# CH340G_PTT.net
KiCad netlist of a schematic drawn in Altium Designer
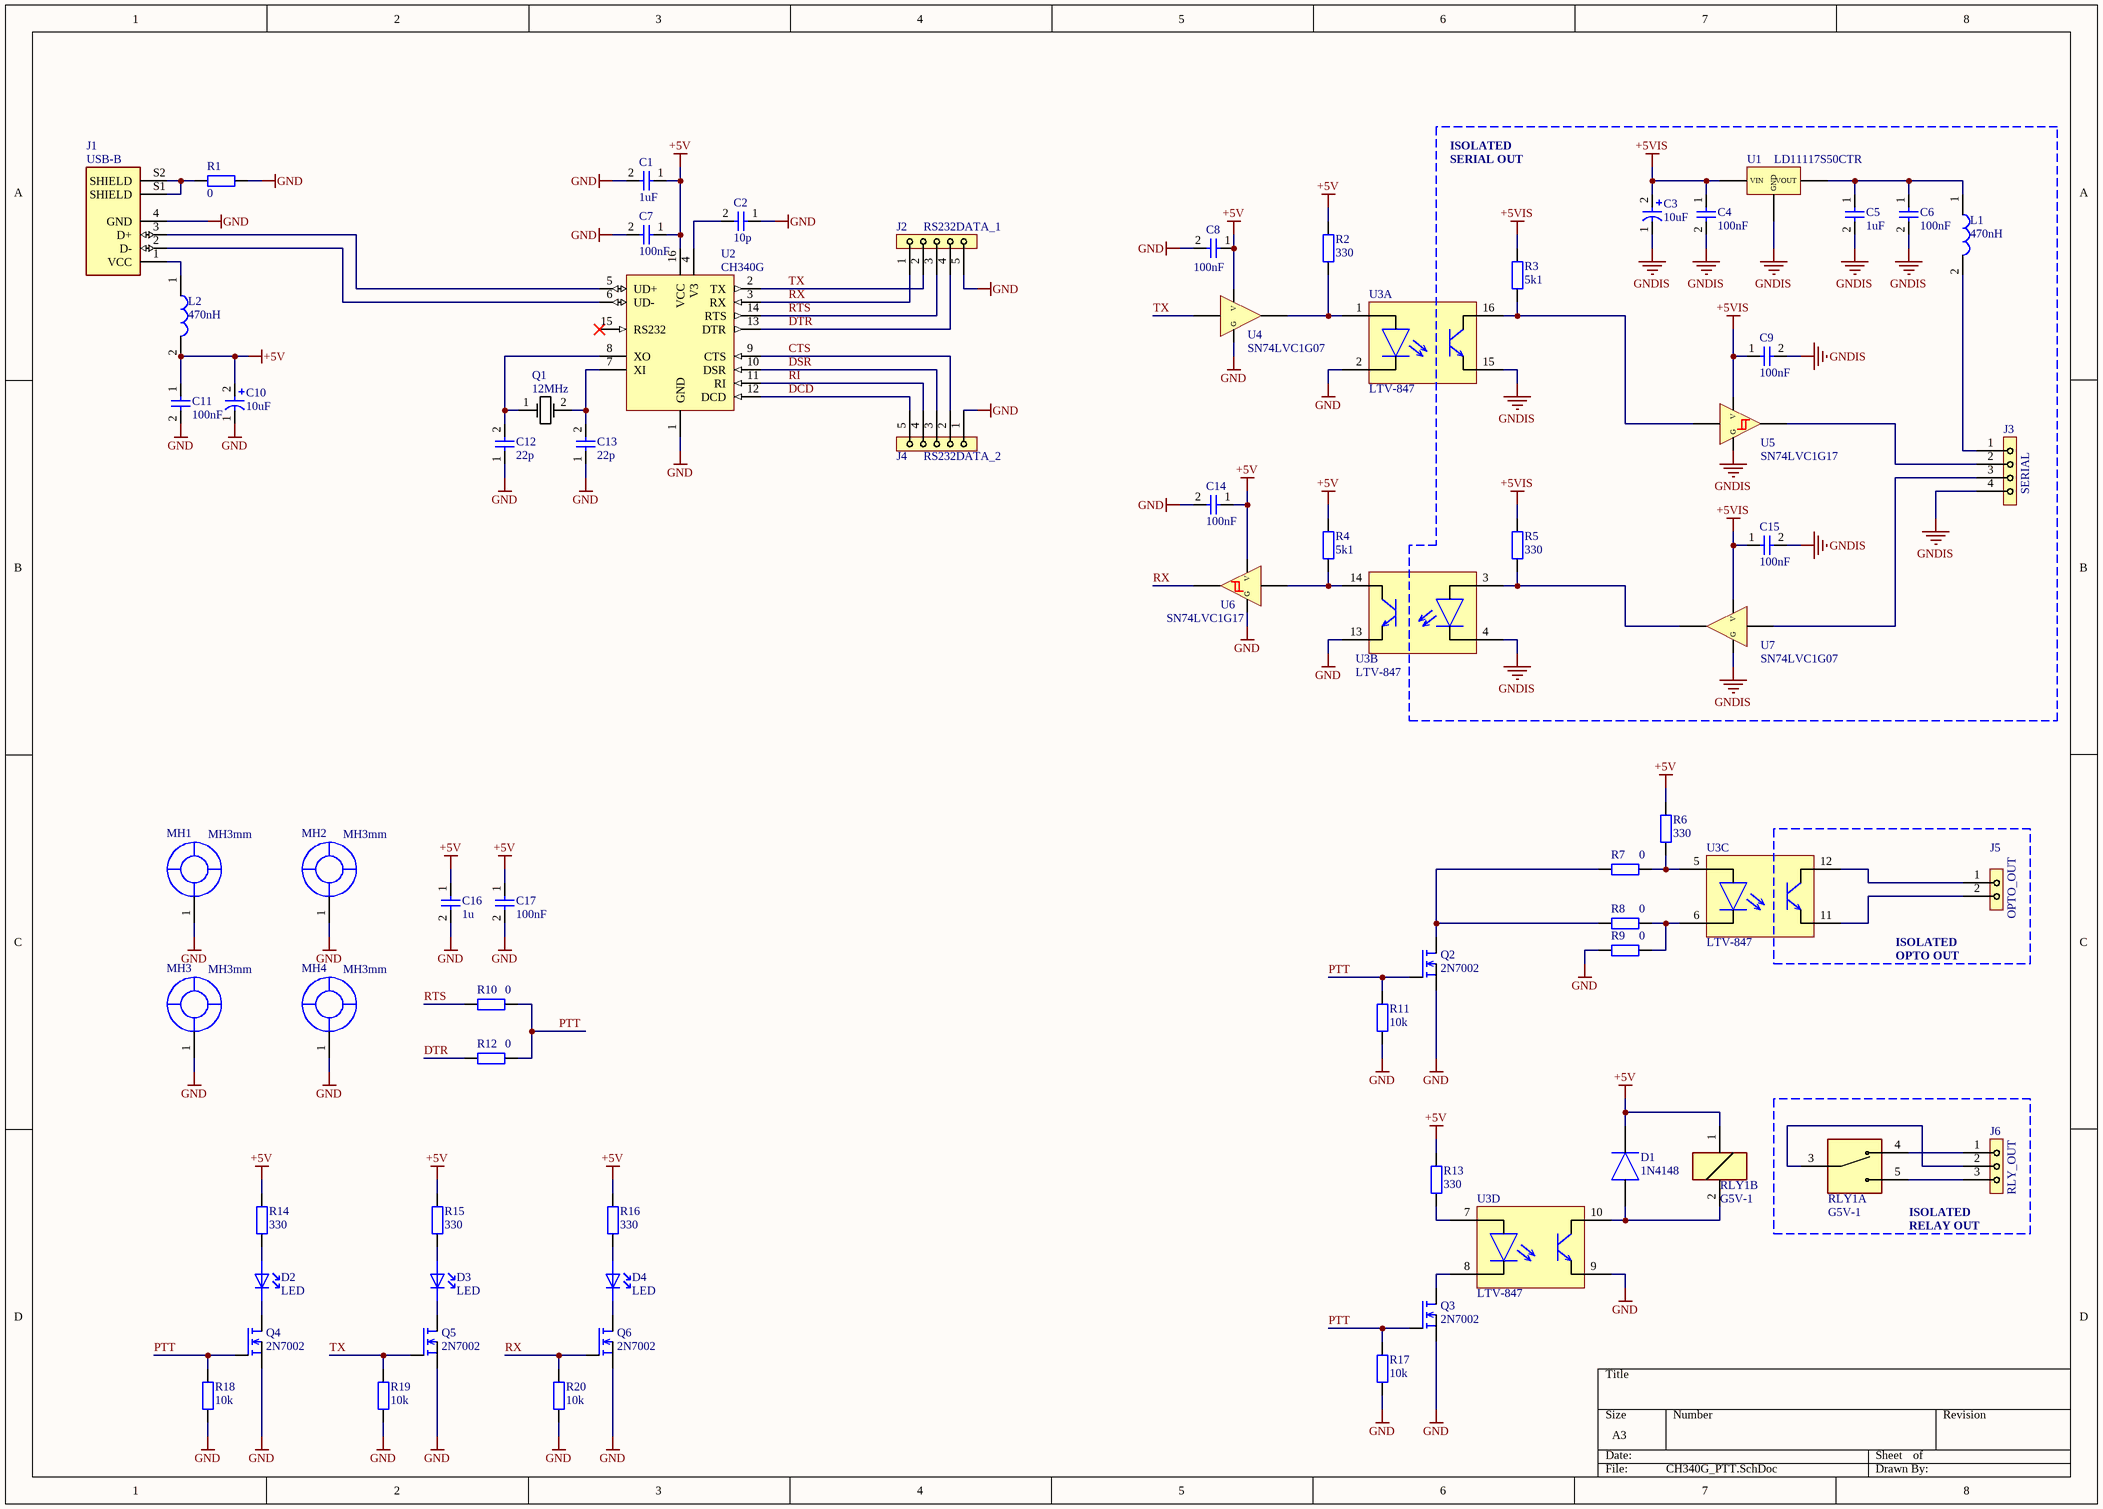
[diagram p0: CH340G_PTT.SchDoc]

(export (version "E")
  (design (tool "Eeschema 10.0.6"))
  (components
    (comp (ref "C1")
      (value "1uF")
      (footprint "FP-1206-L_3_2_0_2-W_1_6_0-IPC_B")
      (libsource (lib "COMM_SHIELD_STUFF") (part "cap_unpol"))
    )
    (comp (ref "C2")
      (value "10p")
      (footprint "FP-1206-L_3_2_0_2-W_1_6_0-IPC_B")
      (libsource (lib "COMM_SHIELD_STUFF") (part "cap_unpol"))
    )
    (comp (ref "C3")
      (value "10uF")
      (footprint "CAP_SMD_6.3x7.7mm")
      (libsource (lib "COMM_SHIELD_STUFF") (part "cap_pol"))
    )
    (comp (ref "C4")
      (value "100nF")
      (footprint "FP-1206-L_3_2_0_2-W_1_6_0-IPC_B")
      (libsource (lib "COMM_SHIELD_STUFF") (part "cap_unpol"))
    )
    (comp (ref "C5")
      (value "1uF")
      (footprint "FP-1206-L_3_2_0_2-W_1_6_0-IPC_B")
      (libsource (lib "COMM_SHIELD_STUFF") (part "cap_unpol"))
    )
    (comp (ref "C6")
      (value "100nF")
      (footprint "FP-1206-L_3_2_0_2-W_1_6_0-IPC_B")
      (libsource (lib "COMM_SHIELD_STUFF") (part "cap_unpol"))
    )
    (comp (ref "C7")
      (value "100nF")
      (footprint "FP-1206-L_3_2_0_2-W_1_6_0-IPC_B")
      (libsource (lib "COMM_SHIELD_STUFF") (part "cap_unpol"))
    )
    (comp (ref "C8")
      (value "100nF")
      (footprint "FP-1206-L_3_2_0_2-W_1_6_0-IPC_B")
      (libsource (lib "COMM_SHIELD_STUFF") (part "cap_unpol"))
    )
    (comp (ref "C9")
      (value "100nF")
      (footprint "FP-1206-L_3_2_0_2-W_1_6_0-IPC_B")
      (libsource (lib "COMM_SHIELD_STUFF") (part "cap_unpol"))
    )
    (comp (ref "C10")
      (value "10uF")
      (footprint "CAP_SMD_6.3x7.7mm")
      (libsource (lib "COMM_SHIELD_STUFF") (part "cap_pol"))
    )
    (comp (ref "C11")
      (value "100nF")
      (footprint "FP-1206-L_3_2_0_2-W_1_6_0-IPC_B")
      (libsource (lib "COMM_SHIELD_STUFF") (part "cap_unpol"))
    )
    (comp (ref "C12")
      (value "22p")
      (footprint "FP-1206-L_3_2_0_2-W_1_6_0-IPC_B")
      (libsource (lib "COMM_SHIELD_STUFF") (part "cap_unpol"))
    )
    (comp (ref "C13")
      (value "22p")
      (footprint "FP-1206-L_3_2_0_2-W_1_6_0-IPC_B")
      (libsource (lib "COMM_SHIELD_STUFF") (part "cap_unpol"))
    )
    (comp (ref "C14")
      (value "100nF")
      (footprint "FP-1206-L_3_2_0_2-W_1_6_0-IPC_B")
      (libsource (lib "COMM_SHIELD_STUFF") (part "cap_unpol"))
    )
    (comp (ref "C15")
      (value "100nF")
      (footprint "FP-1206-L_3_2_0_2-W_1_6_0-IPC_B")
      (libsource (lib "COMM_SHIELD_STUFF") (part "cap_unpol"))
    )
    (comp (ref "C16")
      (value "1u")
      (footprint "FP-1206-L_3_2_0_2-W_1_6_0-IPC_B")
      (libsource (lib "COMM_SHIELD_STUFF") (part "cap_unpol"))
    )
    (comp (ref "C17")
      (value "100nF")
      (footprint "FP-1206-L_3_2_0_2-W_1_6_0-IPC_B")
      (libsource (lib "COMM_SHIELD_STUFF") (part "cap_unpol"))
    )
    (comp (ref "D1")
      (value "1N4148")
      (footprint "SOD80C")
      (libsource (lib "COMM_SHIELD_STUFF") (part "1N4148"))
    )
    (comp (ref "D2")
      (value "LED")
      (footprint "LED_3mm")
      (libsource (lib "COMM_SHIELD_STUFF") (part "LED_3mm"))
    )
    (comp (ref "D3")
      (value "LED")
      (footprint "LED_3mm")
      (libsource (lib "COMM_SHIELD_STUFF") (part "LED_3mm"))
    )
    (comp (ref "D4")
      (value "LED")
      (footprint "LED_3mm")
      (libsource (lib "COMM_SHIELD_STUFF") (part "LED_3mm"))
    )
    (comp (ref "J1")
      (value "USB-B")
      (footprint "USB-B")
      (libsource (lib "COMM_SHIELD_STUFF") (part "USB-B-THT"))
    )
    (comp (ref "J2")
      (value "RS232DATA_1")
      (footprint "PIN_HEADER_1L_5P")
      (libsource (lib "COMM_SHIELD_STUFF") (part "PIN_HEADER_1L_5P"))
    )
    (comp (ref "J3")
      (value "SERIAL")
      (footprint "PIN_HEADER_1L_4P")
      (libsource (lib "COMM_SHIELD_STUFF") (part "PIN_HEADER_1L_4P"))
    )
    (comp (ref "J4")
      (value "RS232DATA_2")
      (footprint "PIN_HEADER_1L_5P")
      (libsource (lib "") (part "PIN_HEADER_1L_5P_1"))
    )
    (comp (ref "J5")
      (value "OPTO_OUT")
      (footprint "PIN_HEADER_1L_2P")
      (libsource (lib "COMM_SHIELD_STUFF") (part "PIN_HEADER_1L_2P"))
    )
    (comp (ref "J6")
      (value "RLY_OUT")
      (footprint "PIN_HEADER_1L_3P")
      (libsource (lib "COMM_SHIELD_STUFF") (part "PIN_HEADER_1L_3P"))
    )
    (comp (ref "L1")
      (value "470nH")
      (footprint "INDC2012X105N")
      (libsource (lib "COMM_SHIELD_STUFF") (part "Inductance"))
    )
    (comp (ref "L2")
      (value "470nH")
      (footprint "INDC2012X105N")
      (libsource (lib "COMM_SHIELD_STUFF") (part "Inductance"))
    )
    (comp (ref "MH1")
      (value "MH3mm")
      (footprint "MOUNTING_HOLE_GROUNDED")
      (description "3.5mm grounded mounting hole")
      (libsource (lib "COMM_SHIELD_STUFF") (part "MOUNTING_HOLE_3.5mm_1"))
    )
    (comp (ref "MH2")
      (value "MH3mm")
      (footprint "MOUNTING_HOLE_GROUNDED")
      (description "3.5mm grounded mounting hole")
      (libsource (lib "COMM_SHIELD_STUFF") (part "MOUNTING_HOLE_3.5mm_1"))
    )
    (comp (ref "MH3")
      (value "MH3mm")
      (footprint "MOUNTING_HOLE_GROUNDED")
      (description "3.5mm grounded mounting hole")
      (libsource (lib "COMM_SHIELD_STUFF") (part "MOUNTING_HOLE_3.5mm_1"))
    )
    (comp (ref "MH4")
      (value "MH3mm")
      (footprint "MOUNTING_HOLE_GROUNDED")
      (description "3.5mm grounded mounting hole")
      (libsource (lib "COMM_SHIELD_STUFF") (part "MOUNTING_HOLE_3.5mm_1"))
    )
    (comp (ref "Q1")
      (value "12MHz")
      (footprint "XTAL_SMD")
      (libsource (lib "COMM_SHIELD_STUFF") (part "Quartz Crystal"))
    )
    (comp (ref "Q2")
      (value "2N7002")
      (footprint "SOT23")
      (libsource (lib "COMM_SHIELD_STUFF") (part "BSS123"))
    )
    (comp (ref "Q3")
      (value "2N7002")
      (footprint "SOT23")
      (libsource (lib "COMM_SHIELD_STUFF") (part "BSS123"))
    )
    (comp (ref "Q4")
      (value "2N7002")
      (footprint "SOT23")
      (libsource (lib "COMM_SHIELD_STUFF") (part "BSS123"))
    )
    (comp (ref "Q5")
      (value "2N7002")
      (footprint "SOT23")
      (libsource (lib "COMM_SHIELD_STUFF") (part "BSS123"))
    )
    (comp (ref "Q6")
      (value "2N7002")
      (footprint "SOT23")
      (libsource (lib "COMM_SHIELD_STUFF") (part "BSS123"))
    )
    (comp (ref "R1")
      (value "0")
      (footprint "FP-CRCW1206-e3-IPC_B")
      (description "EU symbol")
      (fields (field (name "RESISTANCE") "0"))
      (libsource (lib "COMM_SHIELD_STUFF") (part "Resistor"))
    )
    (comp (ref "R2")
      (value "Resistor")
      (footprint "FP-CRCW1206-e3-IPC_B")
      (description "EU symbol")
      (fields (field (name "RESISTANCE") "330"))
      (libsource (lib "COMM_SHIELD_STUFF") (part "Resistor"))
    )
    (comp (ref "R3")
      (value "Resistor")
      (footprint "FP-CRCW1206-e3-IPC_B")
      (description "EU symbol")
      (fields (field (name "RESISTANCE") "5k1"))
      (libsource (lib "COMM_SHIELD_STUFF") (part "Resistor"))
    )
    (comp (ref "R4")
      (value "Resistor")
      (footprint "FP-CRCW1206-e3-IPC_B")
      (description "EU symbol")
      (fields (field (name "RESISTANCE") "5k1"))
      (libsource (lib "COMM_SHIELD_STUFF") (part "Resistor"))
    )
    (comp (ref "R5")
      (value "Resistor")
      (footprint "FP-CRCW1206-e3-IPC_B")
      (description "EU symbol")
      (fields (field (name "RESISTANCE") "330"))
      (libsource (lib "COMM_SHIELD_STUFF") (part "Resistor"))
    )
    (comp (ref "R6")
      (value "Resistor")
      (footprint "FP-CRCW1206-e3-IPC_B")
      (description "EU symbol")
      (fields (field (name "RESISTANCE") "330"))
      (libsource (lib "COMM_SHIELD_STUFF") (part "Resistor"))
    )
    (comp (ref "R7")
      (value "Resistor")
      (footprint "FP-CRCW1206-e3-IPC_B")
      (description "EU symbol")
      (fields (field (name "RESISTANCE") "0"))
      (libsource (lib "COMM_SHIELD_STUFF") (part "Resistor"))
    )
    (comp (ref "R8")
      (value "Resistor")
      (footprint "FP-CRCW1206-e3-IPC_B")
      (description "EU symbol")
      (fields (field (name "RESISTANCE") "0"))
      (libsource (lib "COMM_SHIELD_STUFF") (part "Resistor"))
    )
    (comp (ref "R9")
      (value "Resistor")
      (footprint "FP-CRCW1206-e3-IPC_B")
      (description "EU symbol")
      (fields (field (name "RESISTANCE") "0"))
      (libsource (lib "COMM_SHIELD_STUFF") (part "Resistor"))
    )
    (comp (ref "R10")
      (value "Resistor")
      (footprint "FP-CRCW1206-e3-IPC_B")
      (description "EU symbol")
      (fields (field (name "RESISTANCE") "0"))
      (libsource (lib "COMM_SHIELD_STUFF") (part "Resistor"))
    )
    (comp (ref "R11")
      (value "Resistor")
      (footprint "FP-CRCW1206-e3-IPC_B")
      (description "EU symbol")
      (fields (field (name "RESISTANCE") "10k"))
      (libsource (lib "COMM_SHIELD_STUFF") (part "Resistor"))
    )
    (comp (ref "R12")
      (value "Resistor")
      (footprint "FP-CRCW1206-e3-IPC_B")
      (description "EU symbol")
      (fields (field (name "RESISTANCE") "0"))
      (libsource (lib "COMM_SHIELD_STUFF") (part "Resistor"))
    )
    (comp (ref "R13")
      (value "Resistor")
      (footprint "FP-CRCW1206-e3-IPC_B")
      (description "EU symbol")
      (fields (field (name "RESISTANCE") "330"))
      (libsource (lib "COMM_SHIELD_STUFF") (part "Resistor"))
    )
    (comp (ref "R14")
      (value "Resistor")
      (footprint "FP-CRCW1206-e3-IPC_B")
      (description "EU symbol")
      (fields (field (name "RESISTANCE") "330"))
      (libsource (lib "COMM_SHIELD_STUFF") (part "Resistor"))
    )
    (comp (ref "R15")
      (value "Resistor")
      (footprint "FP-CRCW1206-e3-IPC_B")
      (description "EU symbol")
      (fields (field (name "RESISTANCE") "330"))
      (libsource (lib "COMM_SHIELD_STUFF") (part "Resistor"))
    )
    (comp (ref "R16")
      (value "Resistor")
      (footprint "FP-CRCW1206-e3-IPC_B")
      (description "EU symbol")
      (fields (field (name "RESISTANCE") "330"))
      (libsource (lib "COMM_SHIELD_STUFF") (part "Resistor"))
    )
    (comp (ref "R17")
      (value "Resistor")
      (footprint "FP-CRCW1206-e3-IPC_B")
      (description "EU symbol")
      (fields (field (name "RESISTANCE") "10k"))
      (libsource (lib "COMM_SHIELD_STUFF") (part "Resistor"))
    )
    (comp (ref "R18")
      (value "Resistor")
      (footprint "FP-CRCW1206-e3-IPC_B")
      (description "EU symbol")
      (fields (field (name "RESISTANCE") "10k"))
      (libsource (lib "COMM_SHIELD_STUFF") (part "Resistor"))
    )
    (comp (ref "R19")
      (value "Resistor")
      (footprint "FP-CRCW1206-e3-IPC_B")
      (description "EU symbol")
      (fields (field (name "RESISTANCE") "10k"))
      (libsource (lib "COMM_SHIELD_STUFF") (part "Resistor"))
    )
    (comp (ref "R20")
      (value "Resistor")
      (footprint "FP-CRCW1206-e3-IPC_B")
      (description "EU symbol")
      (fields (field (name "RESISTANCE") "10k"))
      (libsource (lib "COMM_SHIELD_STUFF") (part "Resistor"))
    )
    (comp (ref "RLY1")
      (value "G5V-1")
      (footprint "OMRON-G5V-1")
      (libsource (lib "COMM_SHIELD_STUFF") (part "RELAY_GENERIC_SPDT"))
    )
    (comp (ref "U1")
      (value "LD11117S50CTR")
      (footprint "SOT230P700X180-4N")
      (libsource (lib "COMM_SHIELD_STUFF") (part "LD11117S50CTR"))
    )
    (comp (ref "U2")
      (value "CH340G")
      (footprint "SOIC16")
      (libsource (lib "COMM_SHIELD_STUFF") (part "CH340G"))
    )
    (comp (ref "U3") (value "LTV-847") (footprint "DIP16") (libsource (lib "") (part "LTV-847_1")))
    (comp (ref "U4")
      (value "SN74LVC1G07")
      (footprint "SOT95P280X145-5N")
      (libsource (lib "COMM_SHIELD_STUFF") (part "SN74LVC1G07"))
    )
    (comp (ref "U5")
      (value "SN74LVC1G17")
      (footprint "SOT95P280X145-5N")
      (libsource (lib "COMM_SHIELD_STUFF") (part "SN74LVC1G17"))
    )
    (comp (ref "U6")
      (value "SN74LVC1G17")
      (footprint "SOT95P280X145-5N")
      (libsource (lib "COMM_SHIELD_STUFF") (part "SN74LVC1G17"))
    )
    (comp (ref "U7")
      (value "SN74LVC1G07")
      (footprint "SOT95P280X145-5N")
      (libsource (lib "COMM_SHIELD_STUFF") (part "SN74LVC1G07"))
    )
  )
  (nets
    (net (code "1") (name "+5V") (class "Default")
      (node (ref "C1") (pin "1") (pinfunction "1_1") (pintype "passive"))
      (node (ref "C10") (pin "2") (pinfunction "2_2") (pintype "passive"))
      (node (ref "C11") (pin "1") (pinfunction "1_1") (pintype "passive"))
      (node (ref "C14") (pin "1") (pinfunction "1_1") (pintype "passive"))
      (node (ref "C16") (pin "1") (pinfunction "1_1") (pintype "passive"))
      (node (ref "C17") (pin "1") (pinfunction "1_1") (pintype "passive"))
      (node (ref "C7") (pin "1") (pinfunction "1_1") (pintype "passive"))
      (node (ref "C8") (pin "1") (pinfunction "1_1") (pintype "passive"))
      (node (ref "D1") (pin "2") (pinfunction "K_2") (pintype "passive"))
      (node (ref "L2") (pin "2") (pinfunction "2_2") (pintype "passive"))
      (node (ref "R13") (pin "2") (pinfunction "2_2") (pintype "passive"))
      (node (ref "R14") (pin "2") (pinfunction "2_2") (pintype "passive"))
      (node (ref "R15") (pin "2") (pinfunction "2_2") (pintype "passive"))
      (node (ref "R16") (pin "2") (pinfunction "2_2") (pintype "passive"))
      (node (ref "R2") (pin "2") (pinfunction "2_2") (pintype "passive"))
      (node (ref "R4") (pin "2") (pinfunction "2_2") (pintype "passive"))
      (node (ref "R6") (pin "2") (pinfunction "2_2") (pintype "passive"))
      (node (ref "RLY1") (pin "1") (pinfunction "1_1") (pintype "passive"))
      (node (ref "U2") (pin "16") (pinfunction "VCC_16") (pintype "passive"))
      (node (ref "U4") (pin "5") (pinfunction "V_5") (pintype "passive"))
      (node (ref "U6") (pin "5") (pinfunction "V_5") (pintype "passive"))
    )
    (net (code "2") (name "+5VIS") (class "Default")
      (node (ref "C15") (pin "1") (pinfunction "1_1") (pintype "passive"))
      (node (ref "C3") (pin "2") (pinfunction "2_2") (pintype "passive"))
      (node (ref "C4") (pin "1") (pinfunction "1_1") (pintype "passive"))
      (node (ref "C9") (pin "1") (pinfunction "1_1") (pintype "passive"))
      (node (ref "R3") (pin "2") (pinfunction "2_2") (pintype "passive"))
      (node (ref "R5") (pin "1") (pinfunction "1_1") (pintype "passive"))
      (node (ref "U1") (pin "3") (pinfunction "VIN_3") (pintype "passive"))
      (node (ref "U5") (pin "5") (pinfunction "V_5") (pintype "passive"))
      (node (ref "U7") (pin "5") (pinfunction "V_5") (pintype "passive"))
    )
    (net (code "3") (name "/CTS") (class "Default")
      (node (ref "J4") (pin "2") (pinfunction "2_2") (pintype "passive"))
      (node (ref "U2") (pin "9") (pinfunction "CTS_9") (pintype "input"))
    )
    (net (code "4") (name "/DCD") (class "Default")
      (node (ref "J4") (pin "5") (pinfunction "5_5") (pintype "passive"))
      (node (ref "U2") (pin "12") (pinfunction "DCD_12") (pintype "input"))
    )
    (net (code "5") (name "/DSR") (class "Default")
      (node (ref "J4") (pin "3") (pinfunction "3_3") (pintype "passive"))
      (node (ref "U2") (pin "10") (pinfunction "DSR_10") (pintype "input"))
    )
    (net (code "6") (name "/DTR") (class "Default")
      (node (ref "J2") (pin "4") (pinfunction "4_4") (pintype "passive"))
      (node (ref "R12") (pin "1") (pinfunction "1_1") (pintype "passive"))
      (node (ref "U2") (pin "13") (pinfunction "DTR_13") (pintype "output"))
    )
    (net (code "7") (name "/PTT") (class "Default")
      (node (ref "Q2") (pin "1") (pinfunction "G_1") (pintype "passive"))
      (node (ref "Q3") (pin "1") (pinfunction "G_1") (pintype "passive"))
      (node (ref "Q4") (pin "1") (pinfunction "G_1") (pintype "passive"))
      (node (ref "R10") (pin "2") (pinfunction "2_2") (pintype "passive"))
      (node (ref "R11") (pin "2") (pinfunction "2_2") (pintype "passive"))
      (node (ref "R12") (pin "2") (pinfunction "2_2") (pintype "passive"))
      (node (ref "R17") (pin "2") (pinfunction "2_2") (pintype "passive"))
      (node (ref "R18") (pin "2") (pinfunction "2_2") (pintype "passive"))
    )
    (net (code "8") (name "/RI") (class "Default")
      (node (ref "J4") (pin "4") (pinfunction "4_4") (pintype "passive"))
      (node (ref "U2") (pin "11") (pinfunction "RI_11") (pintype "input"))
    )
    (net (code "9") (name "/RTS") (class "Default")
      (node (ref "J2") (pin "3") (pinfunction "3_3") (pintype "passive"))
      (node (ref "R10") (pin "1") (pinfunction "1_1") (pintype "passive"))
      (node (ref "U2") (pin "14") (pinfunction "RTS_14") (pintype "output"))
    )
    (net (code "10") (name "/RX") (class "Default")
      (node (ref "J2") (pin "1") (pinfunction "1_1") (pintype "passive"))
      (node (ref "Q6") (pin "1") (pinfunction "G_1") (pintype "passive"))
      (node (ref "R20") (pin "2") (pinfunction "2_2") (pintype "passive"))
      (node (ref "U2") (pin "3") (pinfunction "RX_3") (pintype "input"))
      (node (ref "U6") (pin "4") (pinfunction "Y_4") (pintype "passive"))
    )
    (net (code "11") (name "/TX") (class "Default")
      (node (ref "J2") (pin "2") (pinfunction "2_2") (pintype "passive"))
      (node (ref "Q5") (pin "1") (pinfunction "G_1") (pintype "passive"))
      (node (ref "R19") (pin "2") (pinfunction "2_2") (pintype "passive"))
      (node (ref "U2") (pin "2") (pinfunction "TX_2") (pintype "output"))
      (node (ref "U4") (pin "2") (pinfunction "A_2") (pintype "passive"))
    )
    (net (code "12") (name "GND") (class "Default")
      (node (ref "C1") (pin "2") (pinfunction "2_2") (pintype "passive"))
      (node (ref "C10") (pin "1") (pinfunction "1_1") (pintype "passive"))
      (node (ref "C11") (pin "2") (pinfunction "2_2") (pintype "passive"))
      (node (ref "C12") (pin "1") (pinfunction "1_1") (pintype "passive"))
      (node (ref "C13") (pin "1") (pinfunction "1_1") (pintype "passive"))
      (node (ref "C14") (pin "2") (pinfunction "2_2") (pintype "passive"))
      (node (ref "C16") (pin "2") (pinfunction "2_2") (pintype "passive"))
      (node (ref "C17") (pin "2") (pinfunction "2_2") (pintype "passive"))
      (node (ref "C2") (pin "1") (pinfunction "1_1") (pintype "passive"))
      (node (ref "C7") (pin "2") (pinfunction "2_2") (pintype "passive"))
      (node (ref "C8") (pin "2") (pinfunction "2_2") (pintype "passive"))
      (node (ref "J1") (pin "4") (pinfunction "GND_4") (pintype "power_in"))
      (node (ref "J2") (pin "5") (pinfunction "5_5") (pintype "passive"))
      (node (ref "J4") (pin "1") (pinfunction "1_1") (pintype "passive"))
      (node (ref "MH1") (pin "1") (pinfunction "1_1") (pintype "passive"))
      (node (ref "MH2") (pin "1") (pinfunction "1_1") (pintype "passive"))
      (node (ref "MH3") (pin "1") (pinfunction "1_1") (pintype "passive"))
      (node (ref "MH4") (pin "1") (pinfunction "1_1") (pintype "passive"))
      (node (ref "Q2") (pin "3") (pinfunction "S_3") (pintype "passive"))
      (node (ref "Q3") (pin "3") (pinfunction "S_3") (pintype "passive"))
      (node (ref "Q4") (pin "3") (pinfunction "S_3") (pintype "passive"))
      (node (ref "Q5") (pin "3") (pinfunction "S_3") (pintype "passive"))
      (node (ref "Q6") (pin "3") (pinfunction "S_3") (pintype "passive"))
      (node (ref "R1") (pin "2") (pinfunction "2_2") (pintype "passive"))
      (node (ref "R11") (pin "1") (pinfunction "1_1") (pintype "passive"))
      (node (ref "R17") (pin "1") (pinfunction "1_1") (pintype "passive"))
      (node (ref "R18") (pin "1") (pinfunction "1_1") (pintype "passive"))
      (node (ref "R19") (pin "1") (pinfunction "1_1") (pintype "passive"))
      (node (ref "R20") (pin "1") (pinfunction "1_1") (pintype "passive"))
      (node (ref "R9") (pin "1") (pinfunction "1_1") (pintype "passive"))
      (node (ref "U2") (pin "1") (pinfunction "GND_1") (pintype "passive"))
      (node (ref "U3") (pin "13") (pinfunction "E_13") (pintype "passive"))
      (node (ref "U3") (pin "2") (pinfunction "K_2") (pintype "passive"))
      (node (ref "U3") (pin "9") (pinfunction "E_9") (pintype "passive"))
      (node (ref "U4") (pin "3") (pinfunction "G_3") (pintype "passive"))
      (node (ref "U6") (pin "3") (pinfunction "G_3") (pintype "passive"))
    )
    (net (code "13") (name "GNDIS") (class "Default")
      (node (ref "C15") (pin "2") (pinfunction "2_2") (pintype "passive"))
      (node (ref "C3") (pin "1") (pinfunction "1_1") (pintype "passive"))
      (node (ref "C4") (pin "2") (pinfunction "2_2") (pintype "passive"))
      (node (ref "C5") (pin "2") (pinfunction "2_2") (pintype "passive"))
      (node (ref "C6") (pin "2") (pinfunction "2_2") (pintype "passive"))
      (node (ref "C9") (pin "2") (pinfunction "2_2") (pintype "passive"))
      (node (ref "J3") (pin "4") (pinfunction "4_4") (pintype "passive"))
      (node (ref "U1") (pin "1") (pinfunction "GND_1") (pintype "passive"))
      (node (ref "U3") (pin "15") (pinfunction "E_15") (pintype "passive"))
      (node (ref "U3") (pin "4") (pinfunction "K_4") (pintype "passive"))
      (node (ref "U5") (pin "3") (pinfunction "G_3") (pintype "passive"))
      (node (ref "U7") (pin "3") (pinfunction "G_3") (pintype "passive"))
    )
    (net (code "14") (name "Net-(D1-A)") (class "Default")
      (node (ref "D1") (pin "1") (pinfunction "A_1") (pintype "passive"))
      (node (ref "RLY1") (pin "2") (pinfunction "2_2") (pintype "passive"))
      (node (ref "U3") (pin "10") (pinfunction "C_10") (pintype "passive"))
    )
    (net (code "15") (name "Net-(D2-A)") (class "Default")
      (node (ref "D2") (pin "1") (pinfunction "A_1") (pintype "passive"))
      (node (ref "R14") (pin "1") (pinfunction "1_1") (pintype "passive"))
    )
    (net (code "16") (name "Net-(D2-K)") (class "Default")
      (node (ref "D2") (pin "2") (pinfunction "K_2") (pintype "passive"))
      (node (ref "Q4") (pin "2") (pinfunction "D_2") (pintype "passive"))
    )
    (net (code "17") (name "Net-(D3-A)") (class "Default")
      (node (ref "D3") (pin "1") (pinfunction "A_1") (pintype "passive"))
      (node (ref "R15") (pin "1") (pinfunction "1_1") (pintype "passive"))
    )
    (net (code "18") (name "Net-(D3-K)") (class "Default")
      (node (ref "D3") (pin "2") (pinfunction "K_2") (pintype "passive"))
      (node (ref "Q5") (pin "2") (pinfunction "D_2") (pintype "passive"))
    )
    (net (code "19") (name "Net-(D4-A)") (class "Default")
      (node (ref "D4") (pin "1") (pinfunction "A_1") (pintype "passive"))
      (node (ref "R16") (pin "1") (pinfunction "1_1") (pintype "passive"))
    )
    (net (code "20") (name "Net-(D4-K)") (class "Default")
      (node (ref "D4") (pin "2") (pinfunction "K_2") (pintype "passive"))
      (node (ref "Q6") (pin "2") (pinfunction "D_2") (pintype "passive"))
    )
    (net (code "21") (name "Net-(J1-D+)") (class "Default")
      (node (ref "J1") (pin "3") (pinfunction "D+_3") (pintype "bidirectional"))
      (node (ref "U2") (pin "5") (pinfunction "UD+_5") (pintype "bidirectional"))
    )
    (net (code "22") (name "Net-(J1-D-)") (class "Default")
      (node (ref "J1") (pin "2") (pinfunction "D-_2") (pintype "bidirectional"))
      (node (ref "U2") (pin "6") (pinfunction "UD-_6") (pintype "bidirectional"))
    )
    (net (code "23") (name "Net-(J1-SHIELD-PadS1)") (class "Default")
      (node (ref "J1") (pin "S1") (pinfunction "SHIELD_S1") (pintype "passive"))
      (node (ref "J1") (pin "S2") (pinfunction "SHIELD_S2") (pintype "passive"))
      (node (ref "R1") (pin "1") (pinfunction "1_1") (pintype "passive"))
    )
    (net (code "24") (name "Net-(J1-VCC)") (class "Default")
      (node (ref "J1") (pin "1") (pinfunction "VCC_1") (pintype "power_in"))
      (node (ref "L2") (pin "1") (pinfunction "1_1") (pintype "passive"))
    )
    (net (code "25") (name "Net-(J3-Pad1)") (class "Default")
      (node (ref "J3") (pin "1") (pinfunction "1_1") (pintype "passive"))
      (node (ref "L1") (pin "2") (pinfunction "2_2") (pintype "passive"))
    )
    (net (code "26") (name "Net-(J6-Pad1)") (class "Default")
      (node (ref "J6") (pin "1") (pinfunction "1_1") (pintype "passive"))
      (node (ref "RLY1") (pin "4") (pinfunction "4_4") (pintype "passive"))
    )
    (net (code "27") (name "Net-(J6-Pad2)") (class "Default")
      (node (ref "J6") (pin "2") (pinfunction "2_2") (pintype "passive"))
      (node (ref "RLY1") (pin "3") (pinfunction "3_3") (pintype "passive"))
    )
    (net (code "28") (name "Net-(J6-Pad3)") (class "Default")
      (node (ref "J6") (pin "3") (pinfunction "3_3") (pintype "passive"))
      (node (ref "RLY1") (pin "5") (pinfunction "5_5") (pintype "passive"))
    )
    (net (code "29") (name "Net-(Q2-D)") (class "Default")
      (node (ref "Q2") (pin "2") (pinfunction "D_2") (pintype "passive"))
      (node (ref "R7") (pin "1") (pinfunction "1_1") (pintype "passive"))
      (node (ref "R8") (pin "1") (pinfunction "1_1") (pintype "passive"))
    )
    (net (code "30") (name "Net-(Q3-D)") (class "Default")
      (node (ref "Q3") (pin "2") (pinfunction "D_2") (pintype "passive"))
      (node (ref "U3") (pin "8") (pinfunction "K_8") (pintype "passive"))
    )
    (net (code "31") (name "Net-(U1-VOUT)") (class "Default")
      (node (ref "C5") (pin "1") (pinfunction "1_1") (pintype "passive"))
      (node (ref "C6") (pin "1") (pinfunction "1_1") (pintype "passive"))
      (node (ref "L1") (pin "1") (pinfunction "1_1") (pintype "passive"))
      (node (ref "U1") (pin "2") (pinfunction "VOUT_2") (pintype "passive"))
    )
    (net (code "32") (name "Net-(U2-V3)") (class "Default")
      (node (ref "C2") (pin "2") (pinfunction "2_2") (pintype "passive"))
      (node (ref "U2") (pin "4") (pinfunction "V3_4") (pintype "passive"))
    )
    (net (code "33") (name "Net-(U2-XI)") (class "Default")
      (node (ref "C13") (pin "2") (pinfunction "2_2") (pintype "passive"))
      (node (ref "Q1") (pin "2") (pinfunction "2_2") (pintype "passive"))
      (node (ref "U2") (pin "7") (pinfunction "XI_7") (pintype "passive"))
    )
    (net (code "34") (name "Net-(U2-XO)") (class "Default")
      (node (ref "C12") (pin "2") (pinfunction "2_2") (pintype "passive"))
      (node (ref "Q1") (pin "1") (pinfunction "1_1") (pintype "passive"))
      (node (ref "U2") (pin "8") (pinfunction "XO_8") (pintype "passive"))
    )
    (net (code "35") (name "Net-(U3A-A)") (class "Default")
      (node (ref "R2") (pin "1") (pinfunction "1_1") (pintype "passive"))
      (node (ref "U3") (pin "1") (pinfunction "A_1") (pintype "passive"))
      (node (ref "U4") (pin "4") (pinfunction "Y_4") (pintype "passive"))
    )
    (net (code "36") (name "Net-(U3A-C)") (class "Default")
      (node (ref "R3") (pin "1") (pinfunction "1_1") (pintype "passive"))
      (node (ref "U3") (pin "16") (pinfunction "C_16") (pintype "passive"))
      (node (ref "U5") (pin "2") (pinfunction "A_2") (pintype "passive"))
    )
    (net (code "37") (name "Net-(U3B-A)") (class "Default")
      (node (ref "R5") (pin "2") (pinfunction "2_2") (pintype "passive"))
      (node (ref "U3") (pin "3") (pinfunction "A_3") (pintype "passive"))
      (node (ref "U7") (pin "4") (pinfunction "Y_4") (pintype "passive"))
    )
    (net (code "38") (name "Net-(U3B-C)") (class "Default")
      (node (ref "R4") (pin "1") (pinfunction "1_1") (pintype "passive"))
      (node (ref "U3") (pin "14") (pinfunction "C_14") (pintype "passive"))
      (node (ref "U6") (pin "2") (pinfunction "A_2") (pintype "passive"))
    )
    (net (code "39") (name "Net-(U3C-A)") (class "Default")
      (node (ref "R6") (pin "1") (pinfunction "1_1") (pintype "passive"))
      (node (ref "R7") (pin "2") (pinfunction "2_2") (pintype "passive"))
      (node (ref "U3") (pin "5") (pinfunction "A_5") (pintype "passive"))
    )
    (net (code "40") (name "Net-(U3C-C)") (class "Default")
      (node (ref "J5") (pin "1") (pinfunction "1_1") (pintype "passive"))
      (node (ref "U3") (pin "12") (pinfunction "C_12") (pintype "passive"))
    )
    (net (code "41") (name "Net-(U3C-E)") (class "Default")
      (node (ref "J5") (pin "2") (pinfunction "2_2") (pintype "passive"))
      (node (ref "U3") (pin "11") (pinfunction "E_11") (pintype "passive"))
    )
    (net (code "42") (name "Net-(U3C-K)") (class "Default")
      (node (ref "R8") (pin "2") (pinfunction "2_2") (pintype "passive"))
      (node (ref "R9") (pin "2") (pinfunction "2_2") (pintype "passive"))
      (node (ref "U3") (pin "6") (pinfunction "K_6") (pintype "passive"))
    )
    (net (code "43") (name "Net-(U3D-A)") (class "Default")
      (node (ref "R13") (pin "1") (pinfunction "1_1") (pintype "passive"))
      (node (ref "U3") (pin "7") (pinfunction "A_7") (pintype "passive"))
    )
    (net (code "44") (name "Net-(U5-Y)") (class "Default")
      (node (ref "J3") (pin "2") (pinfunction "2_2") (pintype "passive"))
      (node (ref "U5") (pin "4") (pinfunction "Y_4") (pintype "passive"))
    )
    (net (code "45") (name "Net-(U7-A)") (class "Default")
      (node (ref "J3") (pin "3") (pinfunction "3_3") (pintype "passive"))
      (node (ref "U7") (pin "2") (pinfunction "A_2") (pintype "passive"))
    )
    (net (code "46") (name "unconnected-(U2-RS232-Pad15)") (class "Default")
      (node (ref "U2") (pin "15") (pinfunction "RS232_15") (pintype "input+no_connect"))
    )
  )
)
